# PiSpi.net
KiCad netlist of a schematic drawn in EAGLE
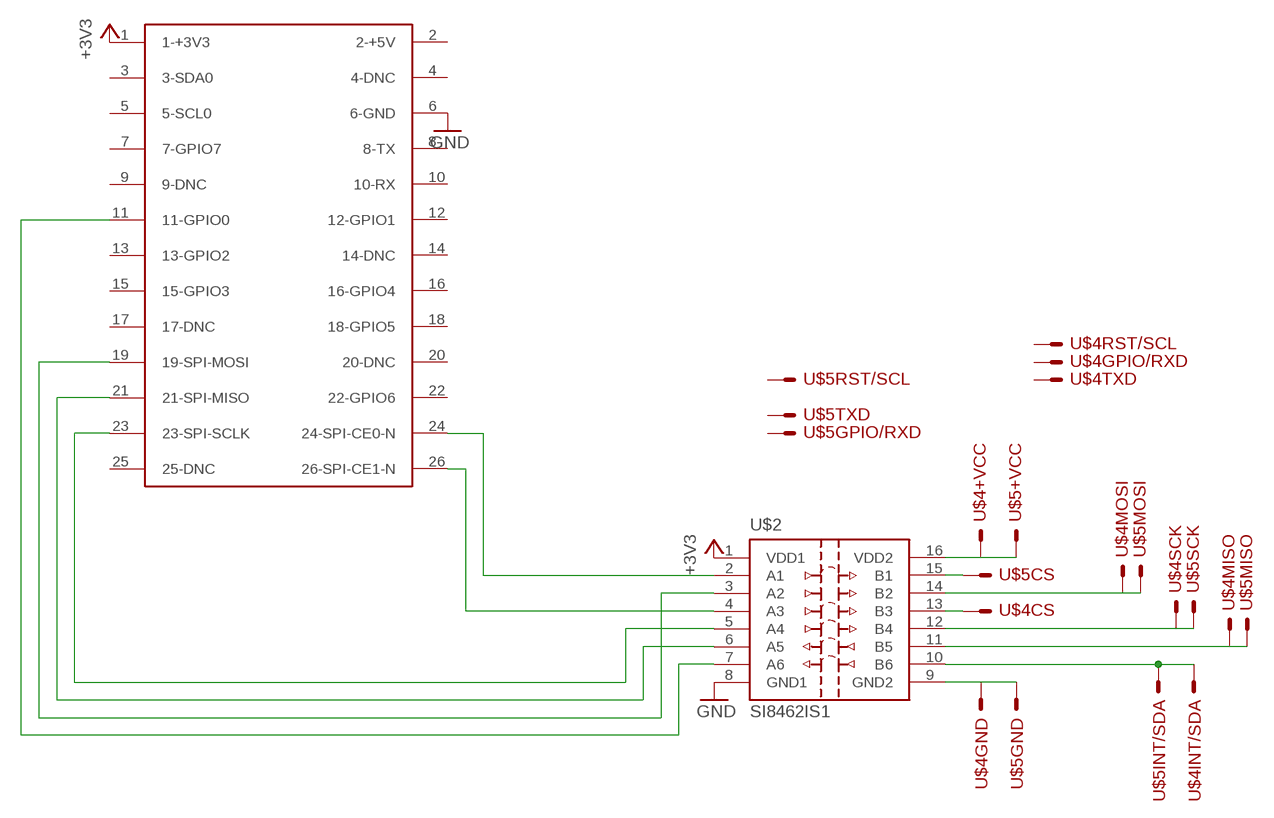
[diagram p0: schematic, sheet 1]

(export (version "E")
  (design (tool "Eeschema 10.0.6"))
  (components
    (comp (ref "U$1")
      (value "RASPBERRY-PI")
      (footprint "eagle-import:RASPBERRY-PI")
      (libsource (lib "eagle-import") (part "RASPBERRY-PI"))
    )
    (comp (ref "U$2")
      (value "SI8462IS1")
      (footprint "eagle-import:SO16")
      (libsource (lib "eagle-import") (part "SI8462IS1"))
    )
    (comp (ref "U$4")
      (value "SPI_BUS2")
      (footprint "eagle-import:SPI_BUS2")
      (libsource (lib "eagle-import") (part "SPI_BUS2"))
    )
    (comp (ref "U$5")
      (value "SPI_BUS2")
      (footprint "eagle-import:SPI_BUS2")
      (libsource (lib "eagle-import") (part "SPI_BUS2"))
    )
  )
  (nets
    (net (code "1") (name "+3V3") (class "Default")
      (node (ref "U$1") (pin "1") (pinfunction "1-+3V3_1") (pintype "bidirectional"))
      (node (ref "U$2") (pin "1") (pinfunction "VDD1_1") (pintype "power_in"))
    )
    (net (code "2") (name "GND") (class "Default")
      (node (ref "U$1") (pin "6") (pinfunction "6-GND_6") (pintype "bidirectional"))
      (node (ref "U$2") (pin "8") (pinfunction "GND1_8") (pintype "power_in"))
    )
    (net (code "3") (name "Net-(U$1-11-GPIO0)") (class "Default")
      (node (ref "U$1") (pin "11") (pinfunction "11-GPIO0_11") (pintype "bidirectional"))
      (node (ref "U$2") (pin "7") (pinfunction "A6_7") (pintype "output"))
    )
    (net (code "4") (name "Net-(U$1-19-SPI-MOSI)") (class "Default")
      (node (ref "U$1") (pin "19") (pinfunction "19-SPI-MOSI_19") (pintype "bidirectional"))
      (node (ref "U$2") (pin "3") (pinfunction "A2_3") (pintype "input"))
    )
    (net (code "5") (name "Net-(U$1-21-SPI-MISO)") (class "Default")
      (node (ref "U$1") (pin "21") (pinfunction "21-SPI-MISO_21") (pintype "bidirectional"))
      (node (ref "U$2") (pin "6") (pinfunction "A5_6") (pintype "output"))
    )
    (net (code "6") (name "Net-(U$1-23-SPI-SCLK)") (class "Default")
      (node (ref "U$1") (pin "23") (pinfunction "23-SPI-SCLK_23") (pintype "bidirectional"))
      (node (ref "U$2") (pin "5") (pinfunction "A4_5") (pintype "input"))
    )
    (net (code "7") (name "Net-(U$1-24-SPI-CE0-N)") (class "Default")
      (node (ref "U$1") (pin "24") (pinfunction "24-SPI-CE0-N_24") (pintype "bidirectional"))
      (node (ref "U$2") (pin "2") (pinfunction "A1_2") (pintype "input"))
    )
    (net (code "8") (name "Net-(U$1-26-SPI-CE1-N)") (class "Default")
      (node (ref "U$1") (pin "26") (pinfunction "26-SPI-CE1-N_26") (pintype "bidirectional"))
      (node (ref "U$2") (pin "4") (pinfunction "A3_4") (pintype "input"))
    )
    (net (code "9") (name "Net-(U$2-B1)") (class "Default")
      (node (ref "U$2") (pin "15") (pinfunction "B1_15") (pintype "output"))
      (node (ref "U$5") (pin "CS") (pinfunction "S_CS") (pintype "passive"))
    )
    (net (code "10") (name "Net-(U$2-B2)") (class "Default")
      (node (ref "U$2") (pin "14") (pinfunction "B2_14") (pintype "output"))
      (node (ref "U$4") (pin "MOSI") (pinfunction "S_MOSI") (pintype "passive"))
      (node (ref "U$5") (pin "MOSI") (pinfunction "S_MOSI") (pintype "passive"))
    )
    (net (code "11") (name "Net-(U$2-B3)") (class "Default")
      (node (ref "U$2") (pin "13") (pinfunction "B3_13") (pintype "output"))
      (node (ref "U$4") (pin "CS") (pinfunction "S_CS") (pintype "passive"))
    )
    (net (code "12") (name "Net-(U$2-B4)") (class "Default")
      (node (ref "U$2") (pin "12") (pinfunction "B4_12") (pintype "output"))
      (node (ref "U$4") (pin "SCK") (pinfunction "S_SCK") (pintype "passive"))
      (node (ref "U$5") (pin "SCK") (pinfunction "S_SCK") (pintype "passive"))
    )
    (net (code "13") (name "Net-(U$2-B5)") (class "Default")
      (node (ref "U$2") (pin "11") (pinfunction "B5_11") (pintype "input"))
      (node (ref "U$4") (pin "MISO") (pinfunction "S_MISO") (pintype "passive"))
      (node (ref "U$5") (pin "MISO") (pinfunction "S_MISO") (pintype "passive"))
    )
    (net (code "14") (name "Net-(U$2-B6)") (class "Default")
      (node (ref "U$2") (pin "10") (pinfunction "B6_10") (pintype "input"))
      (node (ref "U$4") (pin "INT/SDA") (pinfunction "S_INT/SDA") (pintype "passive"))
      (node (ref "U$5") (pin "INT/SDA") (pinfunction "S_INT/SDA") (pintype "passive"))
    )
    (net (code "15") (name "Net-(U$2-GND2)") (class "Default")
      (node (ref "U$2") (pin "9") (pinfunction "GND2_9") (pintype "power_in"))
      (node (ref "U$4") (pin "GND") (pinfunction "S_GND") (pintype "passive"))
      (node (ref "U$5") (pin "GND") (pinfunction "S_GND") (pintype "passive"))
    )
    (net (code "16") (name "Net-(U$2-VDD2)") (class "Default")
      (node (ref "U$2") (pin "16") (pinfunction "VDD2_16") (pintype "power_in"))
      (node (ref "U$4") (pin "+VCC") (pinfunction "S_+VCC") (pintype "passive"))
      (node (ref "U$5") (pin "+VCC") (pinfunction "S_+VCC") (pintype "passive"))
    )
    (net (code "17") (name "unconnected-(U$1-2-+5V-Pad2)") (class "Default")
      (node (ref "U$1") (pin "2") (pinfunction "2-+5V_2") (pintype "bidirectional"))
    )
    (net (code "18") (name "unconnected-(U$1-3-SDA0-Pad3)") (class "Default")
      (node (ref "U$1") (pin "3") (pinfunction "3-SDA0_3") (pintype "bidirectional"))
    )
    (net (code "19") (name "unconnected-(U$1-4-DNC-Pad4)") (class "Default")
      (node (ref "U$1") (pin "4") (pinfunction "4-DNC_4") (pintype "bidirectional"))
    )
    (net (code "20") (name "unconnected-(U$1-5-SCL0-Pad5)") (class "Default")
      (node (ref "U$1") (pin "5") (pinfunction "5-SCL0_5") (pintype "bidirectional"))
    )
    (net (code "21") (name "unconnected-(U$1-7-GPIO7-Pad7)") (class "Default")
      (node (ref "U$1") (pin "7") (pinfunction "7-GPIO7_7") (pintype "bidirectional"))
    )
    (net (code "22") (name "unconnected-(U$1-8-TX-Pad8)") (class "Default")
      (node (ref "U$1") (pin "8") (pinfunction "8-TX_8") (pintype "bidirectional"))
    )
    (net (code "23") (name "unconnected-(U$1-9-DNC-Pad9)") (class "Default")
      (node (ref "U$1") (pin "9") (pinfunction "9-DNC_9") (pintype "bidirectional"))
    )
    (net (code "24") (name "unconnected-(U$1-10-RX-Pad10)") (class "Default")
      (node (ref "U$1") (pin "10") (pinfunction "10-RX_10") (pintype "bidirectional"))
    )
    (net (code "25") (name "unconnected-(U$1-12-GPIO1-Pad12)") (class "Default")
      (node (ref "U$1") (pin "12") (pinfunction "12-GPIO1_12") (pintype "bidirectional"))
    )
    (net (code "26") (name "unconnected-(U$1-13-GPIO2-Pad13)") (class "Default")
      (node (ref "U$1") (pin "13") (pinfunction "13-GPIO2_13") (pintype "bidirectional"))
    )
    (net (code "27") (name "unconnected-(U$1-14-DNC-Pad14)") (class "Default")
      (node (ref "U$1") (pin "14") (pinfunction "14-DNC_14") (pintype "bidirectional"))
    )
    (net (code "28") (name "unconnected-(U$1-15-GPIO3-Pad15)") (class "Default")
      (node (ref "U$1") (pin "15") (pinfunction "15-GPIO3_15") (pintype "bidirectional"))
    )
    (net (code "29") (name "unconnected-(U$1-16-GPIO4-Pad16)") (class "Default")
      (node (ref "U$1") (pin "16") (pinfunction "16-GPIO4_16") (pintype "bidirectional"))
    )
    (net (code "30") (name "unconnected-(U$1-17-DNC-Pad17)") (class "Default")
      (node (ref "U$1") (pin "17") (pinfunction "17-DNC_17") (pintype "bidirectional"))
    )
    (net (code "31") (name "unconnected-(U$1-18-GPIO5-Pad18)") (class "Default")
      (node (ref "U$1") (pin "18") (pinfunction "18-GPIO5_18") (pintype "bidirectional"))
    )
    (net (code "32") (name "unconnected-(U$1-20-DNC-Pad20)") (class "Default")
      (node (ref "U$1") (pin "20") (pinfunction "20-DNC_20") (pintype "bidirectional"))
    )
    (net (code "33") (name "unconnected-(U$1-22-GPIO6-Pad22)") (class "Default")
      (node (ref "U$1") (pin "22") (pinfunction "22-GPIO6_22") (pintype "bidirectional"))
    )
    (net (code "34") (name "unconnected-(U$1-25-DNC-Pad25)") (class "Default")
      (node (ref "U$1") (pin "25") (pinfunction "25-DNC_25") (pintype "bidirectional"))
    )
    (net (code "35") (name "unconnected-(U$4D-S-PadGPIO{slash}RXD)") (class "Default")
      (node (ref "U$4") (pin "GPIO/RXD") (pinfunction "S_GPIO/RXD") (pintype "passive"))
    )
    (net (code "36") (name "unconnected-(U$4H-S-PadRST{slash}SCL)") (class "Default")
      (node (ref "U$4") (pin "RST/SCL") (pinfunction "S_RST/SCL") (pintype "passive"))
    )
    (net (code "37") (name "unconnected-(U$4J-S-PadTXD)") (class "Default")
      (node (ref "U$4") (pin "TXD") (pinfunction "S_TXD") (pintype "passive"))
    )
    (net (code "38") (name "unconnected-(U$5D-S-PadGPIO{slash}RXD)") (class "Default")
      (node (ref "U$5") (pin "GPIO/RXD") (pinfunction "S_GPIO/RXD") (pintype "passive"))
    )
    (net (code "39") (name "unconnected-(U$5H-S-PadRST{slash}SCL)") (class "Default")
      (node (ref "U$5") (pin "RST/SCL") (pinfunction "S_RST/SCL") (pintype "passive"))
    )
    (net (code "40") (name "unconnected-(U$5J-S-PadTXD)") (class "Default")
      (node (ref "U$5") (pin "TXD") (pinfunction "S_TXD") (pintype "passive"))
    )
  )
)
